# MainBoard.net
KiCad netlist of a schematic drawn in Altium Designer
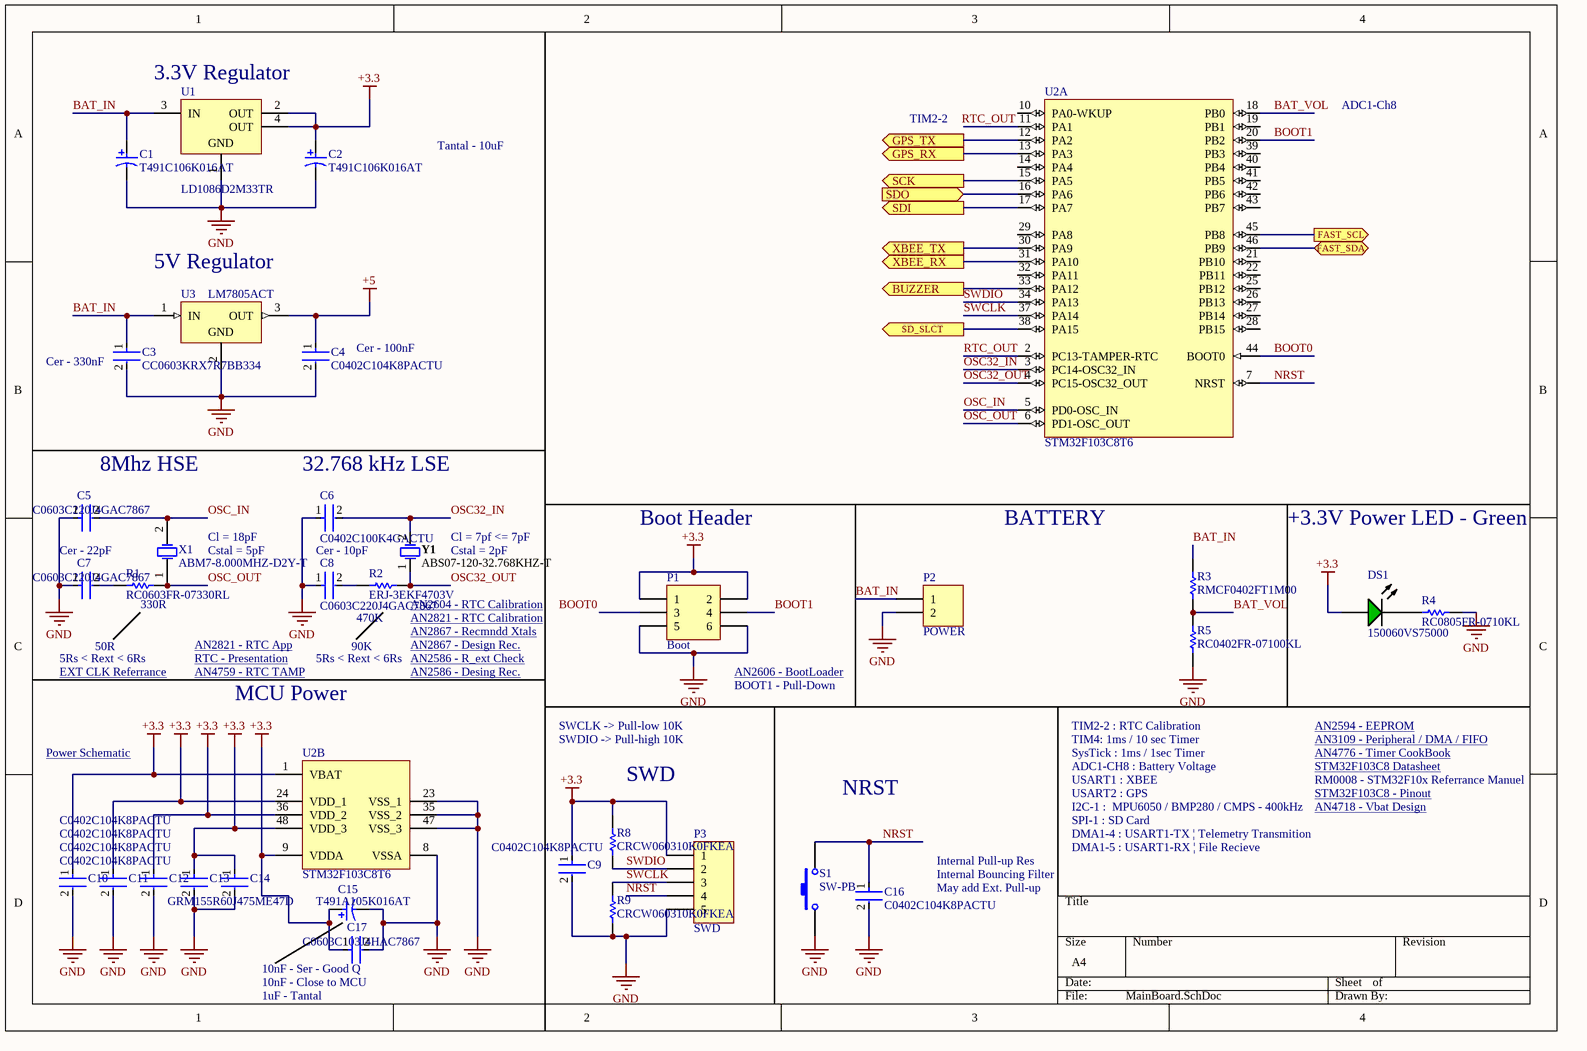
[diagram p0: MainBoard.SchDoc]

(export (version "E")
  (design (tool "Eeschema 10.0.6"))
  (components
    (comp (ref "C1")
      (value "T491C106K016AT")
      (footprint "KEMT-T491-C_L")
      (description "Tantalum Capacitor, 10 uF, +/- 10%, 16 V, -55 to 125 degC, 2-Pin SMD (T491-C), RoHS, Tape and Reel")
      (fields (field (name "VOLTAGE") "16VDC") (field (name "MANUFACTURER") "Kemet"))
      (libsource (lib "Altium Content Vault") (part "CAP-P-2"))
    )
    (comp (ref "C2")
      (value "T491C106K016AT")
      (footprint "KEMT-T491-C_L")
      (description "Tantalum Capacitor, 10 uF, +/- 10%, 16 V, -55 to 125 degC, 2-Pin SMD (T491-C), RoHS, Tape and Reel")
      (fields (field (name "VOLTAGE") "16VDC") (field (name "MANUFACTURER") "Kemet"))
      (libsource (lib "Altium Content Vault") (part "CAP-P-2"))
    )
    (comp (ref "C3")
      (value "CC0603KRX7R7BB334")
      (footprint "FP-CC0603-DA-MFG")
      (description "CAP CER 0.33UF 16V X7R 0603")
      (fields
        (field (name "OCTOPART") "https://octopart.com/cc0603krx7r7bb334-yageo-9291796")
        (field (name "MANUFACTURER") "YAGEO")
      )
      (libsource (lib "Altium Content Vault") (part "11868f565c42a9108669ba33697ecf6"))
    )
    (comp (ref "C4")
      (value "C0402C104K8PACTU")
      (footprint "FP-C0402-BB-MFG")
      (description "CAP CER 0.1UF 10V X5R 0402")
      (fields (field (name "MANUFACTURER") "Kemet") (field (name "TOLERANCE") "0.1"))
      (libsource (lib "Altium Content Vault") (part "b4654b650e69147ec39a6b967a45e02"))
    )
    (comp (ref "C5")
      (value "C0603C220J4GAC7867")
      (footprint "FP-C0603C-CF-MFG")
      (description "CAP CER 22PF 16V NP0 0603")
      (fields
        (field (name "OCTOPART") "https://octopart.com/c0603c220j4gac7867-kemet-1963820")
        (field (name "TOLERANCE") "0.05")
      )
      (libsource (lib "Altium Content Vault") (part "b4654b650e69147ec39a6b967a45e02"))
    )
    (comp (ref "C6")
      (value "C0402C100K4GACTU")
      (footprint "FP-C0402-BB-MFG")
      (description "CAP CER 10PF 16V 10% NP0 0402")
      (fields (field (name "MANUFACTURER") "Kemet") (field (name "TOLERANCE") "0.1"))
      (libsource (lib "Altium Content Vault") (part "b4654b650e69147ec39a6b967a45e02"))
    )
    (comp (ref "C7")
      (value "C0603C220J4GAC7867")
      (footprint "FP-C0603C-CF-MFG")
      (description "CAP CER 22PF 16V NP0 0603")
      (fields
        (field (name "OCTOPART") "https://octopart.com/c0603c220j4gac7867-kemet-1963820")
        (field (name "TOLERANCE") "0.05")
      )
      (libsource (lib "Altium Content Vault") (part "b4654b650e69147ec39a6b967a45e02"))
    )
    (comp (ref "C8")
      (value "C0603C220J4GAC7867")
      (footprint "FP-C0603C-CF-MFG")
      (description "CAP CER 22PF 16V NP0 0603")
      (fields
        (field (name "OCTOPART") "https://octopart.com/c0603c220j4gac7867-kemet-1963820")
        (field (name "TOLERANCE") "0.05")
      )
      (libsource (lib "Altium Content Vault") (part "b4654b650e69147ec39a6b967a45e02"))
    )
    (comp (ref "C9")
      (value "C0402C104K8PACTU")
      (footprint "FP-C0402-BB-MFG")
      (description "CAP CER 0.1UF 10V X5R 0402")
      (fields (field (name "MANUFACTURER") "Kemet") (field (name "TOLERANCE") "0.1"))
      (libsource (lib "Altium Content Vault") (part "b4654b650e69147ec39a6b967a45e02"))
    )
    (comp (ref "C10")
      (value "C0402C104K8PACTU")
      (footprint "FP-C0402-BB-MFG")
      (description "CAP CER 0.1UF 10V X5R 0402")
      (fields (field (name "MANUFACTURER") "Kemet") (field (name "TOLERANCE") "0.1"))
      (libsource (lib "Altium Content Vault") (part "b4654b650e69147ec39a6b967a45e02"))
    )
    (comp (ref "C11")
      (value "C0402C104K8PACTU")
      (footprint "FP-C0402-BB-MFG")
      (description "CAP CER 0.1UF 10V X5R 0402")
      (fields (field (name "MANUFACTURER") "Kemet") (field (name "TOLERANCE") "0.1"))
      (libsource (lib "Altium Content Vault") (part "b4654b650e69147ec39a6b967a45e02"))
    )
    (comp (ref "C12")
      (value "C0402C104K8PACTU")
      (footprint "FP-C0402-BB-MFG")
      (description "CAP CER 0.1UF 10V X5R 0402")
      (fields (field (name "MANUFACTURER") "Kemet") (field (name "TOLERANCE") "0.1"))
      (libsource (lib "Altium Content Vault") (part "b4654b650e69147ec39a6b967a45e02"))
    )
    (comp (ref "C13")
      (value "GRM155R60J475ME47D")
      (footprint "FP-GRM155-0_1-IPC_B")
      (description "Chip Multilayer Ceramic Capacitors for General Purpose, 0402, 4.7uF, X5R, 15%, 20%, 6.3V")
      (fields (field (name "VOLTAGE") "6.3V") (field (name "TOLERANCE") "20%"))
      (libsource (lib "Altium Content Vault") (part "11868f565c42a9108669ba33697ecf6"))
    )
    (comp (ref "C14")
      (value "C0402C104K8PACTU")
      (footprint "FP-C0402-BB-MFG")
      (description "CAP CER 0.1UF 10V X5R 0402")
      (fields (field (name "MANUFACTURER") "Kemet") (field (name "TOLERANCE") "0.1"))
      (libsource (lib "Altium Content Vault") (part "b4654b650e69147ec39a6b967a45e02"))
    )
    (comp (ref "C15")
      (value "T491A105K016AT")
      (footprint "KEMT-T491A105K016AT_L")
      (description "Tantalun Capacitor, 1 uF, +/- 10%, 16 V, -55 to 125 degC, 2-Pin SMD, RoHS, Tape and Reel")
      (fields (field (name "MANUFACTURER") "Kemet") (field (name "TOLERANCE") "±10%"))
      (libsource (lib "Altium Content Vault") (part "CAP-P-2"))
    )
    (comp (ref "C16")
      (value "C0402C104K8PACTU")
      (footprint "FP-C0402-BB-MFG")
      (description "CAP CER 0.1UF 10V X5R 0402")
      (fields (field (name "MANUFACTURER") "Kemet") (field (name "TOLERANCE") "0.1"))
      (libsource (lib "Altium Content Vault") (part "b4654b650e69147ec39a6b967a45e02"))
    )
    (comp (ref "C17")
      (value "C0603C103J4HAC7867")
      (footprint "FP-C0603C-CF-MFG")
      (description "CAP CER 0603 10NF 16V ULTRA STAB")
      (fields (field (name "TOLERANCE") "0.05") (field (name "MANUFACTURER") "KEMET"))
      (libsource (lib "Altium Content Vault") (part "b4654b650e69147ec39a6b967a45e02"))
    )
    (comp (ref "DS1")
      (value "150060VS75000")
      (footprint "WE-150060VS75000_V")
      (libsource (lib "Altium Content Vault") (part "LED_GREEN_K1A2-2"))
    )
    (comp (ref "P1")
      (value "Boot")
      (footprint "HDR2X3")
      (description "Header, 3-Pin, Dual row")
      (fields (field (name "PUBLISHER") "Altium Limited"))
      (libsource (lib "Miscellaneous Connectors") (part "Header 3X2"))
    )
    (comp (ref "P2")
      (value "POWER")
      (footprint "HDR1X2H")
      (description "Header, 2-Pin, Right Angle")
      (fields (field (name "PUBLISHER") "Altium Limited"))
      (libsource (lib "Miscellaneous Connectors") (part "Header 2H"))
    )
    (comp (ref "P3")
      (value "SWD")
      (footprint "HDR1X5")
      (description "Header, 5-Pin")
      (fields (field (name "PUBLISHER") "Altium Limited"))
      (libsource (lib "Miscellaneous Connectors") (part "Header 5"))
    )
    (comp (ref "R1")
      (value "RC0603FR-07330RL")
      (footprint "RESC1608X55X25NL10T15")
      (description "Chip Resistor, 330 Ohm, +/- 1%, 0.1 W, -55 to 155 degC, 0603 (1608 Metric), RoHS, Tape and Reel")
      (fields (field (name "TOLERANCE") "10%"))
      (libsource (lib "Altium Content Vault") (part "RES-2"))
    )
    (comp (ref "R2")
      (value "ERJ-3EKF4703V")
      (footprint "RESC1608X55X30LL15T15")
      (description "Chip Resistor, 470 KOhm, +/- 1%, 0.1 W, -55 to 155 degC, 0603 (1608 Metric), RoHS, Tape and Reel")
      (libsource (lib "Altium Content Vault") (part "RES-2"))
    )
    (comp (ref "R3")
      (value "RMCF0402FT1M00")
      (footprint "RESC1005X40X25LL10T15")
      (description "Chip Resistor, 1 MOhm, +/- 1%, 63 mW, -55 to 155 degC, 0402 (1005 Metric), RoHS, Tape and Reel")
      (fields (field (name "MANUFACTURER") "Stackpole-Electronics-Inc.") (field (name "TOLERANCE") "±1%"))
      (libsource (lib "Altium Content Vault") (part "RES-2"))
    )
    (comp (ref "R4")
      (value "RC0805FR-0710KL")
      (footprint "RESC2013X60X35NL10T20")
      (description "Chip Resistor, 10 KOhm, +/- 1%, 0.125 W, -55 to 155 degC, 0805 (2012 Metric), RoHS, Tape and Reel")
      (fields (field (name "MANUFACTURER") "Yageo"))
      (libsource (lib "Altium Content Vault") (part "RES-2"))
    )
    (comp (ref "R5")
      (value "RC0402FR-07100KL")
      (footprint "RESC1005X40X25NL05T10")
      (fields (field (name "MANUFACTURER") "Yageo / Phycomp"))
      (libsource (lib "Altium Content Vault") (part "RES"))
    )
    (comp (ref "R8")
      (value "CRCW060310K0FKEA")
      (footprint "RESC1609X50X30NL8T20")
      (description "Chip Resistor, 10 KOhm, +/- 1%, 100 mW, -55 to 155 degC, 0603 (1608 Metric), RoHS, Tape and Reel")
      (fields (field (name "MANUFACTURER") "Vishay Semiconductor"))
      (libsource (lib "Altium Content Vault") (part "RES-2"))
    )
    (comp (ref "R9")
      (value "CRCW060310K0FKEA")
      (footprint "RESC1609X50X30NL8T20")
      (description "Chip Resistor, 10 KOhm, +/- 1%, 100 mW, -55 to 155 degC, 0603 (1608 Metric), RoHS, Tape and Reel")
      (fields (field (name "MANUFACTURER") "Vishay Semiconductor"))
      (libsource (lib "Altium Content Vault") (part "RES-2"))
    )
    (comp (ref "S1")
      (value "SW-PB")
      (footprint "SPST-2")
      (description "Switch")
      (fields (field (name "PUBLISHER") "Altium Limited"))
      (libsource (lib "Miscellaneous Devices") (part "SW-PB"))
    )
    (comp (ref "U1")
      (value "LD1086D2M33TR")
      (footprint "D2PAK_A_L")
      (description "1.5A, Low Drop Positive Voltage Regulator, 3.3V, 4-Pin D2PAK/A, Tape and Reel")
      (libsource (lib "Altium Content Vault") (part "PM-REG-LD1085-SOT4"))
    )
    (comp (ref "U2")
      (value "STM32F103C8T6")
      (footprint "STM-LQFP48_L")
      (libsource (lib "Altium Content Vault") (part "MC-ARM-STM32F103X8_B-SQ48"))
    )
    (comp (ref "U3")
      (value "LM7805ACT")
      (footprint "FAIR-TO-220-3")
      (description "Positive Voltage Regulator, 5 V, 1 A, 0 to 125 degC, 3-Pin TO-220, RoHS, Tube")
      (fields (field (name "MANUFACTURER") "Fairchild"))
      (libsource (lib "Altium Content Vault") (part "FAIR-LM7805CT-TO220-3"))
    )
    (comp (ref "X1")
      (value "ABM7-8.000MHZ-D2Y-T")
      (footprint "ABRA-ABM7-2_V")
      (description "Microprocessor Crystal, 8 MHz, 18 PF, -40 to 85 degC, 2-Pin SMD, RoHS, Tape and Reel")
      (fields (field (name "MANUFACTURER") "Abracon"))
      (libsource (lib "Altium Content Vault") (part "XTAL_1-2-2"))
    )
    (comp (ref "Y1")
      (value "ABS07-120-32.768KHZ-T")
      (footprint "ABRA-ABS07_A_V")
      (description "Tuning Fork Crystal, 32.768 KHz, +/- 20 ppm, -40 to 85 degC, 2-Pin SMD, RoHS, Tape and Reel")
      (fields (field (name "MANUFACTURER") "Abracon") (field (name "TOLERANCE") "20ppm"))
      (libsource (lib "Altium Content Vault") (part "XTAL-1-2-2"))
    )
  )
  (nets
    (net (code "1") (name "+3.3") (class "Default")
      (node (ref "C10") (pin "1") (pinfunction "1_1") (pintype "passive"))
      (node (ref "C11") (pin "1") (pinfunction "1_1") (pintype "passive"))
      (node (ref "C12") (pin "1") (pinfunction "1_1") (pintype "passive"))
      (node (ref "C13") (pin "1") (pinfunction "1_1") (pintype "passive"))
      (node (ref "C14") (pin "1") (pinfunction "1_1") (pintype "passive"))
      (node (ref "C15") (pin "1") (pinfunction "1_1") (pintype "passive"))
      (node (ref "C17") (pin "1") (pinfunction "1_1") (pintype "passive"))
      (node (ref "C2") (pin "1") (pinfunction "1_1") (pintype "passive"))
      (node (ref "C9") (pin "1") (pinfunction "1_1") (pintype "passive"))
      (node (ref "DS1") (pin "2") (pinfunction "A_2") (pintype "passive"))
      (node (ref "P1") (pin "1") (pinfunction "1_1") (pintype "passive"))
      (node (ref "P1") (pin "2") (pinfunction "2_2") (pintype "passive"))
      (node (ref "P3") (pin "1") (pinfunction "1_1") (pintype "passive"))
      (node (ref "R8") (pin "2") (pinfunction "2_2") (pintype "passive"))
      (node (ref "U1") (pin "2") (pinfunction "OUT_2") (pintype "power_in"))
      (node (ref "U1") (pin "4") (pinfunction "OUT_4") (pintype "power_in"))
      (node (ref "U2") (pin "1") (pinfunction "VBAT_1") (pintype "power_in"))
      (node (ref "U2") (pin "24") (pinfunction "VDD_1_24") (pintype "power_in"))
      (node (ref "U2") (pin "36") (pinfunction "VDD_2_36") (pintype "power_in"))
      (node (ref "U2") (pin "48") (pinfunction "VDD_3_48") (pintype "power_in"))
      (node (ref "U2") (pin "9") (pinfunction "VDDA_9") (pintype "power_in"))
    )
    (net (code "2") (name "+5") (class "Default")
      (node (ref "C4") (pin "1") (pinfunction "1_1") (pintype "passive"))
      (node (ref "U3") (pin "3") (pinfunction "OUT_3") (pintype "output"))
    )
    (net (code "3") (name "/BAT_IN") (class "Default")
      (node (ref "C1") (pin "1") (pinfunction "1_1") (pintype "passive"))
      (node (ref "C3") (pin "1") (pinfunction "1_1") (pintype "passive"))
      (node (ref "P2") (pin "1") (pinfunction "1_1") (pintype "passive"))
      (node (ref "R3") (pin "2") (pinfunction "2_2") (pintype "passive"))
      (node (ref "U1") (pin "3") (pinfunction "IN_3") (pintype "power_in"))
      (node (ref "U3") (pin "1") (pinfunction "IN_1") (pintype "input"))
    )
    (net (code "4") (name "/BAT_VOL") (class "Default")
      (node (ref "R3") (pin "1") (pinfunction "1_1") (pintype "passive"))
      (node (ref "R5") (pin "2") (pinfunction "2_2") (pintype "passive"))
      (node (ref "U2") (pin "18") (pinfunction "PB0_18") (pintype "bidirectional"))
    )
    (net (code "5") (name "/BOOT0") (class "Default")
      (node (ref "P1") (pin "3") (pinfunction "3_3") (pintype "passive"))
      (node (ref "U2") (pin "44") (pinfunction "BOOT0_44") (pintype "input"))
    )
    (net (code "6") (name "/BOOT1") (class "Default")
      (node (ref "P1") (pin "4") (pinfunction "4_4") (pintype "passive"))
      (node (ref "U2") (pin "20") (pinfunction "PB2_20") (pintype "bidirectional"))
    )
    (net (code "7") (name "/BUZZER") (class "Default")
      (node (ref "U2") (pin "33") (pinfunction "PA12_33") (pintype "bidirectional"))
    )
    (net (code "8") (name "/FAST_SCL") (class "Default")
      (node (ref "U2") (pin "45") (pinfunction "PB8_45") (pintype "bidirectional"))
    )
    (net (code "9") (name "/FAST_SDA") (class "Default")
      (node (ref "U2") (pin "46") (pinfunction "PB9_46") (pintype "bidirectional"))
    )
    (net (code "10") (name "/GPS_RX") (class "Default")
      (node (ref "U2") (pin "13") (pinfunction "PA3_13") (pintype "bidirectional"))
    )
    (net (code "11") (name "/GPS_TX") (class "Default")
      (node (ref "U2") (pin "12") (pinfunction "PA2_12") (pintype "bidirectional"))
    )
    (net (code "12") (name "/NRST") (class "Default")
      (node (ref "C16") (pin "1") (pinfunction "1_1") (pintype "passive"))
      (node (ref "P3") (pin "4") (pinfunction "4_4") (pintype "passive"))
      (node (ref "S1") (pin "2") (pinfunction "2_2") (pintype "passive"))
      (node (ref "U2") (pin "7") (pinfunction "NRST_7") (pintype "bidirectional"))
    )
    (net (code "13") (name "/OSC32_IN") (class "Default")
      (node (ref "C6") (pin "2") (pinfunction "2_2") (pintype "passive"))
      (node (ref "U2") (pin "3") (pinfunction "PC14-OSC32_IN_3") (pintype "bidirectional"))
      (node (ref "Y1") (pin "2") (pinfunction "2_2") (pintype "passive"))
    )
    (net (code "14") (name "/OSC32_OUT") (class "Default")
      (node (ref "R2") (pin "2") (pinfunction "2_2") (pintype "passive"))
      (node (ref "U2") (pin "4") (pinfunction "PC15-OSC32_OUT_4") (pintype "bidirectional"))
      (node (ref "Y1") (pin "1") (pinfunction "1_1") (pintype "passive"))
    )
    (net (code "15") (name "/OSC_IN") (class "Default")
      (node (ref "C5") (pin "2") (pinfunction "2_2") (pintype "passive"))
      (node (ref "U2") (pin "5") (pinfunction "PD0-OSC_IN_5") (pintype "bidirectional"))
      (node (ref "X1") (pin "2") (pinfunction "X2_2") (pintype "passive"))
    )
    (net (code "16") (name "/OSC_OUT") (class "Default")
      (node (ref "R1") (pin "2") (pinfunction "2_2") (pintype "passive"))
      (node (ref "U2") (pin "6") (pinfunction "PD1-OSC_OUT_6") (pintype "bidirectional"))
      (node (ref "X1") (pin "1") (pinfunction "X1_1") (pintype "passive"))
    )
    (net (code "17") (name "/RTC_OUT") (class "Default")
      (node (ref "U2") (pin "11") (pinfunction "PA1_11") (pintype "bidirectional"))
      (node (ref "U2") (pin "2") (pinfunction "PC13-TAMPER-RTC_2") (pintype "bidirectional"))
    )
    (net (code "18") (name "/SCK") (class "Default")
      (node (ref "U2") (pin "15") (pinfunction "PA5_15") (pintype "bidirectional"))
    )
    (net (code "19") (name "/SDI") (class "Default")
      (node (ref "U2") (pin "17") (pinfunction "PA7_17") (pintype "bidirectional"))
    )
    (net (code "20") (name "/SDO") (class "Default")
      (node (ref "U2") (pin "16") (pinfunction "PA6_16") (pintype "bidirectional"))
    )
    (net (code "21") (name "/SD_SLCT") (class "Default")
      (node (ref "U2") (pin "38") (pinfunction "PA15_38") (pintype "bidirectional"))
    )
    (net (code "22") (name "/SWCLK") (class "Default")
      (node (ref "P3") (pin "3") (pinfunction "3_3") (pintype "passive"))
      (node (ref "R9") (pin "2") (pinfunction "2_2") (pintype "passive"))
      (node (ref "U2") (pin "37") (pinfunction "PA14_37") (pintype "bidirectional"))
    )
    (net (code "23") (name "/SWDIO") (class "Default")
      (node (ref "P3") (pin "2") (pinfunction "2_2") (pintype "passive"))
      (node (ref "R8") (pin "1") (pinfunction "1_1") (pintype "passive"))
      (node (ref "U2") (pin "34") (pinfunction "PA13_34") (pintype "bidirectional"))
    )
    (net (code "24") (name "/XBEE_RX") (class "Default")
      (node (ref "U2") (pin "31") (pinfunction "PA10_31") (pintype "bidirectional"))
    )
    (net (code "25") (name "/XBEE_TX") (class "Default")
      (node (ref "U2") (pin "30") (pinfunction "PA9_30") (pintype "bidirectional"))
    )
    (net (code "26") (name "GND") (class "Default")
      (node (ref "C1") (pin "2") (pinfunction "2_2") (pintype "passive"))
      (node (ref "C10") (pin "2") (pinfunction "2_2") (pintype "passive"))
      (node (ref "C11") (pin "2") (pinfunction "2_2") (pintype "passive"))
      (node (ref "C12") (pin "2") (pinfunction "2_2") (pintype "passive"))
      (node (ref "C13") (pin "2") (pinfunction "2_2") (pintype "passive"))
      (node (ref "C14") (pin "2") (pinfunction "2_2") (pintype "passive"))
      (node (ref "C15") (pin "2") (pinfunction "2_2") (pintype "passive"))
      (node (ref "C16") (pin "2") (pinfunction "2_2") (pintype "passive"))
      (node (ref "C17") (pin "2") (pinfunction "2_2") (pintype "passive"))
      (node (ref "C2") (pin "2") (pinfunction "2_2") (pintype "passive"))
      (node (ref "C3") (pin "2") (pinfunction "2_2") (pintype "passive"))
      (node (ref "C4") (pin "2") (pinfunction "2_2") (pintype "passive"))
      (node (ref "C5") (pin "1") (pinfunction "1_1") (pintype "passive"))
      (node (ref "C6") (pin "1") (pinfunction "1_1") (pintype "passive"))
      (node (ref "C7") (pin "1") (pinfunction "1_1") (pintype "passive"))
      (node (ref "C8") (pin "1") (pinfunction "1_1") (pintype "passive"))
      (node (ref "C9") (pin "2") (pinfunction "2_2") (pintype "passive"))
      (node (ref "P1") (pin "5") (pinfunction "5_5") (pintype "passive"))
      (node (ref "P1") (pin "6") (pinfunction "6_6") (pintype "passive"))
      (node (ref "P2") (pin "2") (pinfunction "2_2") (pintype "passive"))
      (node (ref "P3") (pin "5") (pinfunction "5_5") (pintype "passive"))
      (node (ref "R4") (pin "2") (pinfunction "2_2") (pintype "passive"))
      (node (ref "R5") (pin "1") (pinfunction "1_1") (pintype "passive"))
      (node (ref "R9") (pin "1") (pinfunction "1_1") (pintype "passive"))
      (node (ref "S1") (pin "1") (pinfunction "1_1") (pintype "passive"))
      (node (ref "U1") (pin "1") (pinfunction "GND_1") (pintype "power_in"))
      (node (ref "U2") (pin "23") (pinfunction "VSS_1_23") (pintype "power_in"))
      (node (ref "U2") (pin "35") (pinfunction "VSS_2_35") (pintype "power_in"))
      (node (ref "U2") (pin "47") (pinfunction "VSS_3_47") (pintype "power_in"))
      (node (ref "U2") (pin "8") (pinfunction "VSSA_8") (pintype "power_in"))
      (node (ref "U3") (pin "2") (pinfunction "GND_2") (pintype "power_in"))
    )
    (net (code "27") (name "Net-(C7-Pad2)") (class "Default")
      (node (ref "C7") (pin "2") (pinfunction "2_2") (pintype "passive"))
      (node (ref "R1") (pin "1") (pinfunction "1_1") (pintype "passive"))
    )
    (net (code "28") (name "Net-(C8-Pad2)") (class "Default")
      (node (ref "C8") (pin "2") (pinfunction "2_2") (pintype "passive"))
      (node (ref "R2") (pin "1") (pinfunction "1_1") (pintype "passive"))
    )
    (net (code "29") (name "Net-(DS1-K)") (class "Default")
      (node (ref "DS1") (pin "1") (pinfunction "K_1") (pintype "passive"))
      (node (ref "R4") (pin "1") (pinfunction "1_1") (pintype "passive"))
    )
    (net (code "30") (name "unconnected-(U2A-PA0-WKUP-Pad10)") (class "Default")
      (node (ref "U2") (pin "10") (pinfunction "PA0-WKUP_10") (pintype "bidirectional"))
    )
    (net (code "31") (name "unconnected-(U2A-PA4-Pad14)") (class "Default")
      (node (ref "U2") (pin "14") (pinfunction "PA4_14") (pintype "bidirectional"))
    )
    (net (code "32") (name "unconnected-(U2A-PA8-Pad29)") (class "Default")
      (node (ref "U2") (pin "29") (pinfunction "PA8_29") (pintype "bidirectional"))
    )
    (net (code "33") (name "unconnected-(U2A-PA11-Pad32)") (class "Default")
      (node (ref "U2") (pin "32") (pinfunction "PA11_32") (pintype "bidirectional"))
    )
    (net (code "34") (name "unconnected-(U2A-PB1-Pad19)") (class "Default")
      (node (ref "U2") (pin "19") (pinfunction "PB1_19") (pintype "bidirectional"))
    )
    (net (code "35") (name "unconnected-(U2A-PB3-Pad39)") (class "Default")
      (node (ref "U2") (pin "39") (pinfunction "PB3_39") (pintype "bidirectional"))
    )
    (net (code "36") (name "unconnected-(U2A-PB4-Pad40)") (class "Default")
      (node (ref "U2") (pin "40") (pinfunction "PB4_40") (pintype "bidirectional"))
    )
    (net (code "37") (name "unconnected-(U2A-PB5-Pad41)") (class "Default")
      (node (ref "U2") (pin "41") (pinfunction "PB5_41") (pintype "bidirectional"))
    )
    (net (code "38") (name "unconnected-(U2A-PB6-Pad42)") (class "Default")
      (node (ref "U2") (pin "42") (pinfunction "PB6_42") (pintype "bidirectional"))
    )
    (net (code "39") (name "unconnected-(U2A-PB7-Pad43)") (class "Default")
      (node (ref "U2") (pin "43") (pinfunction "PB7_43") (pintype "bidirectional"))
    )
    (net (code "40") (name "unconnected-(U2A-PB10-Pad21)") (class "Default")
      (node (ref "U2") (pin "21") (pinfunction "PB10_21") (pintype "bidirectional"))
    )
    (net (code "41") (name "unconnected-(U2A-PB11-Pad22)") (class "Default")
      (node (ref "U2") (pin "22") (pinfunction "PB11_22") (pintype "bidirectional"))
    )
    (net (code "42") (name "unconnected-(U2A-PB12-Pad25)") (class "Default")
      (node (ref "U2") (pin "25") (pinfunction "PB12_25") (pintype "bidirectional"))
    )
    (net (code "43") (name "unconnected-(U2A-PB13-Pad26)") (class "Default")
      (node (ref "U2") (pin "26") (pinfunction "PB13_26") (pintype "bidirectional"))
    )
    (net (code "44") (name "unconnected-(U2A-PB14-Pad27)") (class "Default")
      (node (ref "U2") (pin "27") (pinfunction "PB14_27") (pintype "bidirectional"))
    )
    (net (code "45") (name "unconnected-(U2A-PB15-Pad28)") (class "Default")
      (node (ref "U2") (pin "28") (pinfunction "PB15_28") (pintype "bidirectional"))
    )
  )
)
